# Power.net
KiCad netlist of a schematic drawn in Altium Designer
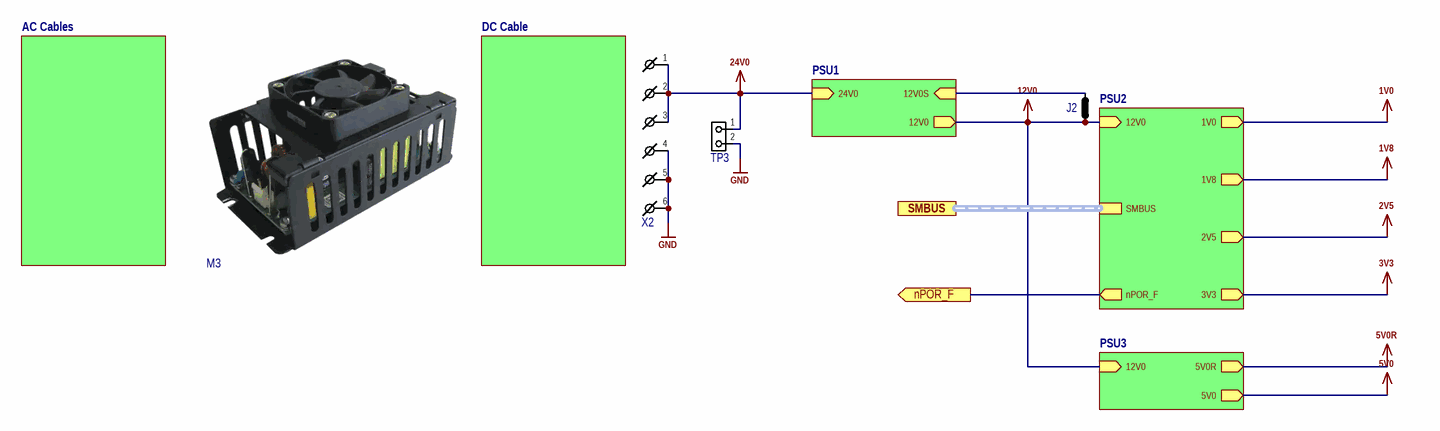
[diagram p0: Power.SchDoc]

(export (version "E")
  (design (tool "Eeschema 10.0.6"))
  (components
    (comp (ref "J2")
      (value "J")
      (footprint "NT0201")
      (description "Net Tie")
      (fields (field (name "13. CREATED DATE/NAME") "AUG2018/Hören"))
      (libsource (lib "chickenfood") (part "NT"))
    )
    (comp (ref "M3")
      (value "CUS150M-24/F")
      (description "AC DC CONVERTER 85~264VAC --> 24VDC (6A)")
      (fields
        (field (name "02. DISTRIBUTOR PART NUMBER") "285-3030-ND")
        (field (name "07. MANUFACTURER  PART NUMBER") "CUS150M24/F")
        (field (name "13. CREATED DATE/NAME") "AUG 2018 / Hören")
      )
      (libsource (lib "PCB-Tester-Board-V1") (part "CUS150M-24/F"))
    )
    (comp (ref "TP3")
      (value "TP")
      (footprint "DualTestpoint 100mils")
      (description "Dual testpoint, pitch 2.54mm")
      (fields
        (field (name "02. DISTRIBUTOR PART NUMBER") "HMTSW-103-07-G-S-240")
        (field (name "13. CREATED DATE/NAME") "AUG2018/Hören")
      )
      (libsource (lib "PCB-Tester-Board-V1") (part "DualTestpoint 100mils"))
    )
    (comp (ref "X2")
      (value "X")
      (footprint "B6PS-VH")
      (description "CONN HEADER R/A 6POS 3.96MM")
      (fields
        (field (name "02. DISTRIBUTOR PART NUMBER") "455-1652-ND")
        (field (name "07. MANUFACTURER  PART NUMBER") "B6PS-VH(LF)(SN)")
        (field (name "13. CREATED DATE/NAME") "AUG 2018 / Hören")
      )
      (libsource (lib "Connectors") (part "B6PS-VH"))
    )
  )
  (nets
    (net (code "2") (name "/12V0S") (class "Default")
      (node (ref "J2") (pin "2") (pinfunction "2_2") (pintype "passive"))
    )
    (net (code "11") (name "12V0") (class "Default")
      (node (ref "J2") (pin "1") (pinfunction "1_1") (pintype "passive"))
    )
    (net (code "12") (name "24V0") (class "Default")
      (node (ref "TP3") (pin "1") (pinfunction "1_1") (pintype "passive"))
      (node (ref "X2") (pin "1") (pinfunction "1_1") (pintype "passive"))
      (node (ref "X2") (pin "2") (pinfunction "2_2") (pintype "passive"))
      (node (ref "X2") (pin "3") (pinfunction "3_3") (pintype "passive"))
    )
    (net (code "13") (name "GND") (class "Default")
      (node (ref "TP3") (pin "2") (pinfunction "2_2") (pintype "passive"))
      (node (ref "X2") (pin "4") (pinfunction "4_4") (pintype "passive"))
      (node (ref "X2") (pin "5") (pinfunction "5_5") (pintype "passive"))
      (node (ref "X2") (pin "6") (pinfunction "6_6") (pintype "passive"))
    )
  )
)
